# FLEXQCMV1_5.net
KiCad netlist of a schematic drawn in EAGLE
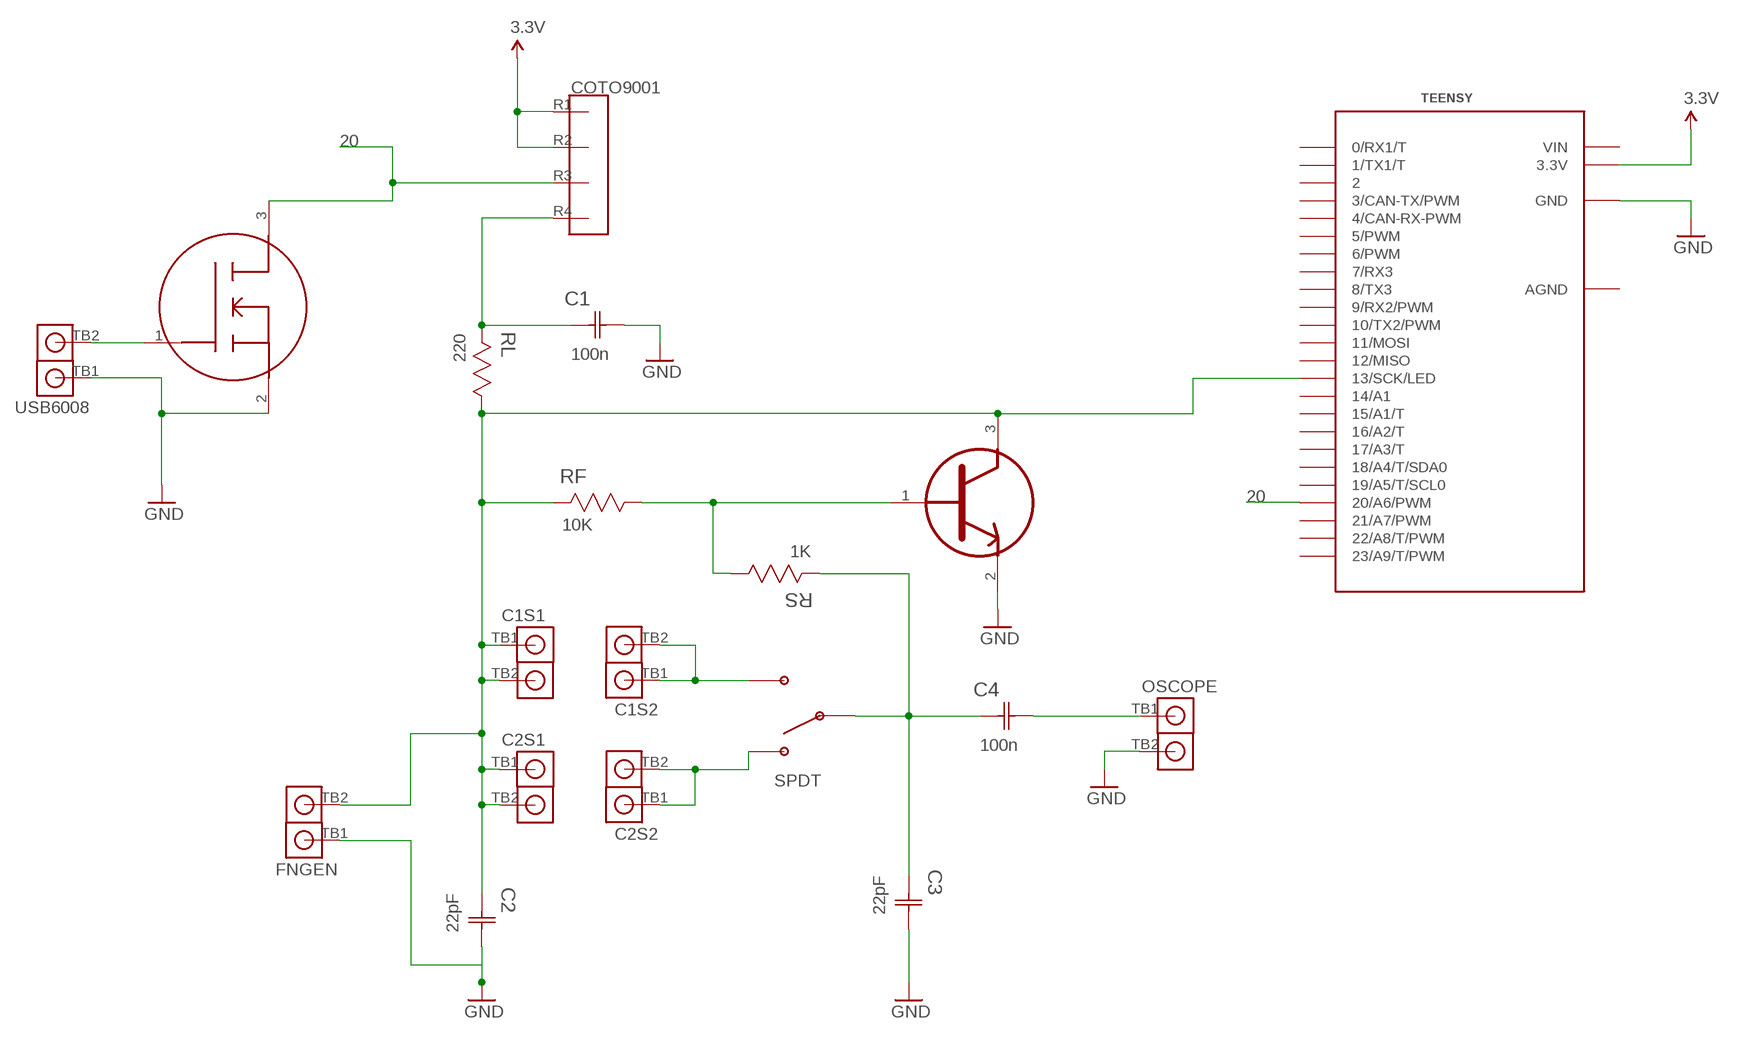
[diagram p0: schematic, sheet 1]

(export (version "E")
  (design (tool "Eeschema 10.0.6"))
  (components
    (comp (ref "C1")
      (value "100n")
      (footprint "eagle-import:CAPC3216X88N")
      (fields (field (name "MPN") "C1206C104K1RACTU") (field (name "TOLERANCE") "±10%"))
      (libsource (lib "eagle-import") (part "C1206C104K1RACTU"))
    )
    (comp (ref "C1S1")
      (value "TERMBLOCKX2")
      (footprint "eagle-import:TERMBLOCKX2")
      (libsource (lib "eagle-import") (part "TERMBLOCKX2"))
    )
    (comp (ref "C1S2")
      (value "TERMBLOCKX2")
      (footprint "eagle-import:TERMBLOCKX2")
      (libsource (lib "eagle-import") (part "TERMBLOCKX2"))
    )
    (comp (ref "C2")
      (value "22pF")
      (footprint "eagle-import:CAPC3216X88N")
      (fields (field (name "MPN") "C1206C220J5GACTU") (field (name "TOLERANCE") "±5%"))
      (libsource (lib "eagle-import") (part "C1206C220J5GACTU"))
    )
    (comp (ref "C2S1")
      (value "TERMBLOCKX2")
      (footprint "eagle-import:TERMBLOCKX2")
      (libsource (lib "eagle-import") (part "TERMBLOCKX2"))
    )
    (comp (ref "C2S2")
      (value "TERMBLOCKX2")
      (footprint "eagle-import:TERMBLOCKX2")
      (libsource (lib "eagle-import") (part "TERMBLOCKX2"))
    )
    (comp (ref "C3")
      (value "22pF")
      (footprint "eagle-import:CAPC3216X88N")
      (fields (field (name "MPN") "C1206C220J5GACTU") (field (name "TOLERANCE") "±5%"))
      (libsource (lib "eagle-import") (part "C1206C220J5GACTU"))
    )
    (comp (ref "C4")
      (value "100n")
      (footprint "eagle-import:CAPC3216X88N")
      (fields (field (name "MPN") "C1206C104K1RACTU") (field (name "TOLERANCE") "±10%"))
      (libsource (lib "eagle-import") (part "C1206C104K1RACTU"))
    )
    (comp (ref "COTO9001")
      (value "COTO9001")
      (footprint "eagle-import:COTO9001")
      (libsource (lib "eagle-import") (part "COTO9001"))
    )
    (comp (ref "FNGEN")
      (value "TERMBLOCKX2")
      (footprint "eagle-import:TERMBLOCKX2")
      (libsource (lib "eagle-import") (part "TERMBLOCKX2"))
    )
    (comp (ref "OSCOPE")
      (value "TERMBLOCKX2")
      (footprint "eagle-import:TERMBLOCKX2")
      (libsource (lib "eagle-import") (part "TERMBLOCKX2"))
    )
    (comp (ref "RF")
      (value "10K")
      (footprint "eagle-import:RESC3216X71N")
      (fields (field (name "MPN") "CRCW120610K0FKEA") (field (name "TOLERANCE") "±1%"))
      (libsource (lib "eagle-import") (part "CRCW120610K0FKEA"))
    )
    (comp (ref "RL")
      (value "220")
      (footprint "eagle-import:RESC3216X71N")
      (fields (field (name "MPN") "CRCW1206220RJNEA") (field (name "TOLERANCE") "±5%"))
      (libsource (lib "eagle-import") (part "CRCW1206220RJNEA"))
    )
    (comp (ref "RS")
      (value "1K")
      (footprint "eagle-import:RESC3216X71N")
      (fields (field (name "MPN") "CRCW12061K00FKEA") (field (name "TOLERANCE") "±1%"))
      (libsource (lib "eagle-import") (part "CRCW12061K00FKEA"))
    )
    (comp (ref "SPDT")
      (value "SPDTSWITCH")
      (footprint "eagle-import:SPDTSWITCH")
      (libsource (lib "eagle-import") (part "SPDTSWITCH"))
    )
    (comp (ref "TEENSY")
      (value "TEENSY_3.1_DIL")
      (footprint "eagle-import:TEENSY3-DIL")
      (libsource (lib "eagle-import") (part "TEENSY_3.1_DIL"))
    )
    (comp (ref "U1")
      (value "FET")
      (footprint "eagle-import:SOT95P230X110-3N")
      (fields (field (name "MPN") "2N7002K"))
      (libsource (lib "eagle-import") (part "2N7002K"))
    )
    (comp (ref "U2")
      (value "BJT")
      (footprint "eagle-import:SOT95P230X110-3N")
      (libsource (lib "eagle-import") (part "BC847C"))
    )
    (comp (ref "USB6008")
      (value "TERMBLOCKX2")
      (footprint "eagle-import:TERMBLOCKX2")
      (libsource (lib "eagle-import") (part "TERMBLOCKX2"))
    )
  )
  (nets
    (net (code "1") (name "/20") (class "Default")
      (node (ref "COTO9001") (pin "R3") (pinfunction "R3_R3") (pintype "bidirectional"))
      (node (ref "TEENSY") (pin "20/A6") (pinfunction "20/A6/PWM_20/A6") (pintype "bidirectional"))
      (node (ref "U1") (pin "3") (pinfunction "D_3") (pintype "bidirectional"))
    )
    (net (code "2") (name "/AGND") (class "Default")
      (node (ref "TEENSY") (pin "AGND") (pinfunction "AGND_AGND") (pintype "power_in"))
    )
    (net (code "3") (name "/VIN") (class "Default")
      (node (ref "TEENSY") (pin "VIN") (pinfunction "VIN_VIN") (pintype "power_in"))
    )
    (net (code "4") (name "3.3V") (class "Default")
      (node (ref "COTO9001") (pin "R1") (pinfunction "R1_R1") (pintype "bidirectional"))
      (node (ref "COTO9001") (pin "R2") (pinfunction "R2_R2") (pintype "bidirectional"))
      (node (ref "TEENSY") (pin "3.3V") (pinfunction "3.3V_3.3V") (pintype "power_in"))
    )
    (net (code "5") (name "GND") (class "Default")
      (node (ref "C1") (pin "2") (pinfunction "C2_2") (pintype "passive"))
      (node (ref "C2") (pin "2") (pinfunction "C2_2") (pintype "passive"))
      (node (ref "C3") (pin "2") (pinfunction "C2_2") (pintype "passive"))
      (node (ref "FNGEN") (pin "TB1") (pinfunction "TB1_TB1") (pintype "bidirectional"))
      (node (ref "OSCOPE") (pin "TB2") (pinfunction "TB2_TB2") (pintype "bidirectional"))
      (node (ref "TEENSY") (pin "GND") (pinfunction "GND_GND") (pintype "power_in"))
      (node (ref "U1") (pin "2") (pinfunction "S_2") (pintype "bidirectional"))
      (node (ref "U2") (pin "2") (pinfunction "E_2") (pintype "bidirectional"))
      (node (ref "USB6008") (pin "TB1") (pinfunction "TB1_TB1") (pintype "bidirectional"))
    )
    (net (code "6") (name "Net-(C1-C1)") (class "Default")
      (node (ref "C1") (pin "1") (pinfunction "C1_1") (pintype "passive"))
      (node (ref "COTO9001") (pin "R4") (pinfunction "R4_R4") (pintype "bidirectional"))
      (node (ref "RL") (pin "2") (pinfunction "2_2") (pintype "passive"))
    )
    (net (code "7") (name "Net-(C1S2-PadTB1)") (class "Default")
      (node (ref "C1S2") (pin "TB1") (pinfunction "TB1_TB1") (pintype "bidirectional"))
      (node (ref "C1S2") (pin "TB2") (pinfunction "TB2_TB2") (pintype "bidirectional"))
      (node (ref "SPDT") (pin "SW3") (pinfunction "SW3_SW3") (pintype "bidirectional"))
    )
    (net (code "8") (name "Net-(C2-C1)") (class "Default")
      (node (ref "C1S1") (pin "TB1") (pinfunction "TB1_TB1") (pintype "bidirectional"))
      (node (ref "C1S1") (pin "TB2") (pinfunction "TB2_TB2") (pintype "bidirectional"))
      (node (ref "C2") (pin "1") (pinfunction "C1_1") (pintype "passive"))
      (node (ref "C2S1") (pin "TB1") (pinfunction "TB1_TB1") (pintype "bidirectional"))
      (node (ref "C2S1") (pin "TB2") (pinfunction "TB2_TB2") (pintype "bidirectional"))
      (node (ref "FNGEN") (pin "TB2") (pinfunction "TB2_TB2") (pintype "bidirectional"))
      (node (ref "RF") (pin "2") (pinfunction "2_2") (pintype "passive"))
      (node (ref "RL") (pin "1") (pinfunction "1_1") (pintype "passive"))
      (node (ref "TEENSY") (pin "13") (pinfunction "13/SCK/LED_13") (pintype "bidirectional"))
      (node (ref "U2") (pin "3") (pinfunction "C_3") (pintype "bidirectional"))
    )
    (net (code "9") (name "Net-(C2S2-PadTB1)") (class "Default")
      (node (ref "C2S2") (pin "TB1") (pinfunction "TB1_TB1") (pintype "bidirectional"))
      (node (ref "C2S2") (pin "TB2") (pinfunction "TB2_TB2") (pintype "bidirectional"))
      (node (ref "SPDT") (pin "SW1") (pinfunction "SW1_SW1") (pintype "bidirectional"))
    )
    (net (code "10") (name "Net-(C3-C1)") (class "Default")
      (node (ref "C3") (pin "1") (pinfunction "C1_1") (pintype "passive"))
      (node (ref "C4") (pin "1") (pinfunction "C1_1") (pintype "passive"))
      (node (ref "RS") (pin "2") (pinfunction "2_2") (pintype "passive"))
      (node (ref "SPDT") (pin "SW2") (pinfunction "SW2_SW2") (pintype "bidirectional"))
    )
    (net (code "11") (name "Net-(C4-C2)") (class "Default")
      (node (ref "C4") (pin "2") (pinfunction "C2_2") (pintype "passive"))
      (node (ref "OSCOPE") (pin "TB1") (pinfunction "TB1_TB1") (pintype "bidirectional"))
    )
    (net (code "12") (name "Net-(U1-G)") (class "Default")
      (node (ref "U1") (pin "1") (pinfunction "G_1") (pintype "bidirectional"))
      (node (ref "USB6008") (pin "TB2") (pinfunction "TB2_TB2") (pintype "bidirectional"))
    )
    (net (code "13") (name "Net-(U2-B)") (class "Default")
      (node (ref "RF") (pin "1") (pinfunction "1_1") (pintype "passive"))
      (node (ref "RS") (pin "1") (pinfunction "1_1") (pintype "passive"))
      (node (ref "U2") (pin "1") (pinfunction "B_1") (pintype "bidirectional"))
    )
    (net (code "14") (name "unconnected-(TEENSY-0{slash}RX1{slash}T-Pad0)") (class "Default")
      (node (ref "TEENSY") (pin "0") (pinfunction "0/RX1/T_0") (pintype "bidirectional"))
    )
    (net (code "15") (name "unconnected-(TEENSY-1{slash}TX1{slash}T-Pad1)") (class "Default")
      (node (ref "TEENSY") (pin "1") (pinfunction "1/TX1/T_1") (pintype "bidirectional"))
    )
    (net (code "16") (name "unconnected-(TEENSY-3{slash}CAN-TX{slash}PWM-Pad3)") (class "Default")
      (node (ref "TEENSY") (pin "3") (pinfunction "3/CAN-TX/PWM_3") (pintype "bidirectional"))
    )
    (net (code "17") (name "unconnected-(TEENSY-4{slash}CAN-RX-PWM-Pad4)") (class "Default")
      (node (ref "TEENSY") (pin "4") (pinfunction "4/CAN-RX-PWM_4") (pintype "bidirectional"))
    )
    (net (code "18") (name "unconnected-(TEENSY-5{slash}PWM-Pad5)") (class "Default")
      (node (ref "TEENSY") (pin "5") (pinfunction "5/PWM_5") (pintype "bidirectional"))
    )
    (net (code "19") (name "unconnected-(TEENSY-6{slash}PWM-Pad6)") (class "Default")
      (node (ref "TEENSY") (pin "6") (pinfunction "6/PWM_6") (pintype "bidirectional"))
    )
    (net (code "20") (name "unconnected-(TEENSY-7{slash}RX3-Pad7)") (class "Default")
      (node (ref "TEENSY") (pin "7") (pinfunction "7/RX3_7") (pintype "bidirectional"))
    )
    (net (code "21") (name "unconnected-(TEENSY-8{slash}TX3-Pad8)") (class "Default")
      (node (ref "TEENSY") (pin "8") (pinfunction "8/TX3_8") (pintype "bidirectional"))
    )
    (net (code "22") (name "unconnected-(TEENSY-9{slash}RX2{slash}PWM-Pad9)") (class "Default")
      (node (ref "TEENSY") (pin "9") (pinfunction "9/RX2/PWM_9") (pintype "bidirectional"))
    )
    (net (code "23") (name "unconnected-(TEENSY-10{slash}TX2{slash}PWM-Pad10)") (class "Default")
      (node (ref "TEENSY") (pin "10") (pinfunction "10/TX2/PWM_10") (pintype "bidirectional"))
    )
    (net (code "24") (name "unconnected-(TEENSY-11{slash}MOSI-Pad11)") (class "Default")
      (node (ref "TEENSY") (pin "11") (pinfunction "11/MOSI_11") (pintype "bidirectional"))
    )
    (net (code "25") (name "unconnected-(TEENSY-12{slash}MISO-Pad12)") (class "Default")
      (node (ref "TEENSY") (pin "12") (pinfunction "12/MISO_12") (pintype "bidirectional"))
    )
    (net (code "26") (name "unconnected-(TEENSY-14{slash}A1-Pad14{slash}A0)") (class "Default")
      (node (ref "TEENSY") (pin "14/A0") (pinfunction "14/A1_14/A0") (pintype "bidirectional"))
    )
    (net (code "27") (name "unconnected-(TEENSY-15{slash}A1{slash}T-Pad15{slash}A1)") (class "Default")
      (node (ref "TEENSY") (pin "15/A1") (pinfunction "15/A1/T_15/A1") (pintype "bidirectional"))
    )
    (net (code "28") (name "unconnected-(TEENSY-16{slash}A2{slash}T-Pad16{slash}A2)") (class "Default")
      (node (ref "TEENSY") (pin "16/A2") (pinfunction "16/A2/T_16/A2") (pintype "bidirectional"))
    )
    (net (code "29") (name "unconnected-(TEENSY-17{slash}A3{slash}T-Pad17{slash}A3)") (class "Default")
      (node (ref "TEENSY") (pin "17/A3") (pinfunction "17/A3/T_17/A3") (pintype "bidirectional"))
    )
    (net (code "30") (name "unconnected-(TEENSY-18{slash}A4{slash}T{slash}SDA0-Pad18{slash}A4)") (class "Default")
      (node (ref "TEENSY") (pin "18/A4") (pinfunction "18/A4/T/SDA0_18/A4") (pintype "bidirectional"))
    )
    (net (code "31") (name "unconnected-(TEENSY-19{slash}A5{slash}T{slash}SCL0-Pad19{slash}A5)") (class "Default")
      (node (ref "TEENSY") (pin "19/A5") (pinfunction "19/A5/T/SCL0_19/A5") (pintype "bidirectional"))
    )
    (net (code "32") (name "unconnected-(TEENSY-21{slash}A7{slash}PWM-Pad21{slash}A7)") (class "Default")
      (node (ref "TEENSY") (pin "21/A7") (pinfunction "21/A7/PWM_21/A7") (pintype "bidirectional"))
    )
    (net (code "33") (name "unconnected-(TEENSY-22{slash}A8{slash}T{slash}PWM-Pad22{slash}A8)") (class "Default")
      (node (ref "TEENSY") (pin "22/A8") (pinfunction "22/A8/T/PWM_22/A8") (pintype "bidirectional"))
    )
    (net (code "34") (name "unconnected-(TEENSY-23{slash}A9{slash}T{slash}PWM-Pad23{slash}A9)") (class "Default")
      (node (ref "TEENSY") (pin "23/A9") (pinfunction "23/A9/T/PWM_23/A9") (pintype "bidirectional"))
    )
    (net (code "35") (name "unconnected-(TEENSY-Pad2)") (class "Default")
      (node (ref "TEENSY") (pin "2") (pinfunction "2_2") (pintype "bidirectional"))
    )
  )
)
